# design.net
KiCad netlist of a schematic drawn in Altium Designer
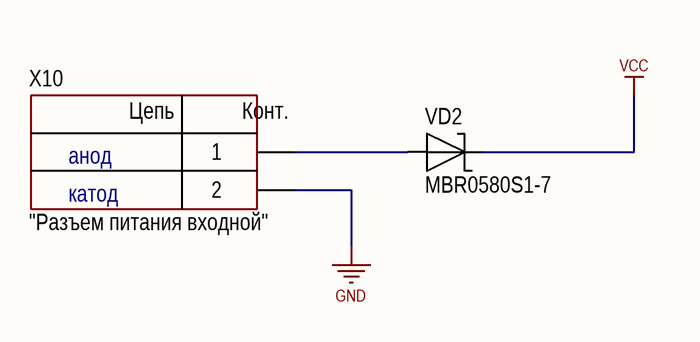
[diagram p0: Узел входного разъёма питания.SchDoc]

(export (version "E")
  (design (tool "Eeschema 10.0.6"))
  (components
    (comp (ref "VD2")
      (value "~")
      (footprint "DIODE: SMC")
      (fields
        (field (name "MANUFACTURER") "Diodes Incorporated")
        (field (name "VALUEMANUFACTURERPARTNUMBER") "Schottky diode, 80V, 500mA, 1V, 15pF, SOD-123, -55...+150°C")
        (field (name "VOLTAGE") "80V")
        (field (name "PARTNUMBER") "MBR0580S1-7")
      )
      (libsource (lib "diode") (part "Schottky_single"))
    )
    (comp (ref "X10")
      (value "~")
      (footprint "CON: DG350-3.5-02P")
      (fields
        (field (name "MANUFACTURER") "Degson")
        (field (name "VALUEMANUFACTURERPARTNUMBER") "Terminal connector, 2pin, 3.5mm, 300VAC, 10A")
        (field (name "PARTNUMBER") "DG350-3.5-02P-14")
        (field (name "COMMENTTEXT") "\"Разъем питания входной\"")
      )
      (libsource (lib "connector") (part "Connector_terminal_2pin"))
    )
  )
  (nets
    (net (code "1") (name "GND") (class "Default")
      (node (ref "X10") (pin "2") (pinfunction "2_2") (pintype "passive"))
    )
    (net (code "2") (name "Net-(VD2-Pad1)") (class "Default")
      (node (ref "VD2") (pin "1") (pinfunction "1_1") (pintype "passive"))
      (node (ref "X10") (pin "1") (pinfunction "1_1") (pintype "passive"))
    )
    (net (code "3") (name "VCC") (class "Default")
      (node (ref "VD2") (pin "2") (pinfunction "2_2") (pintype "passive"))
    )
  )
)
